# Busboard_v10.net
KiCad netlist of a schematic drawn in EAGLE
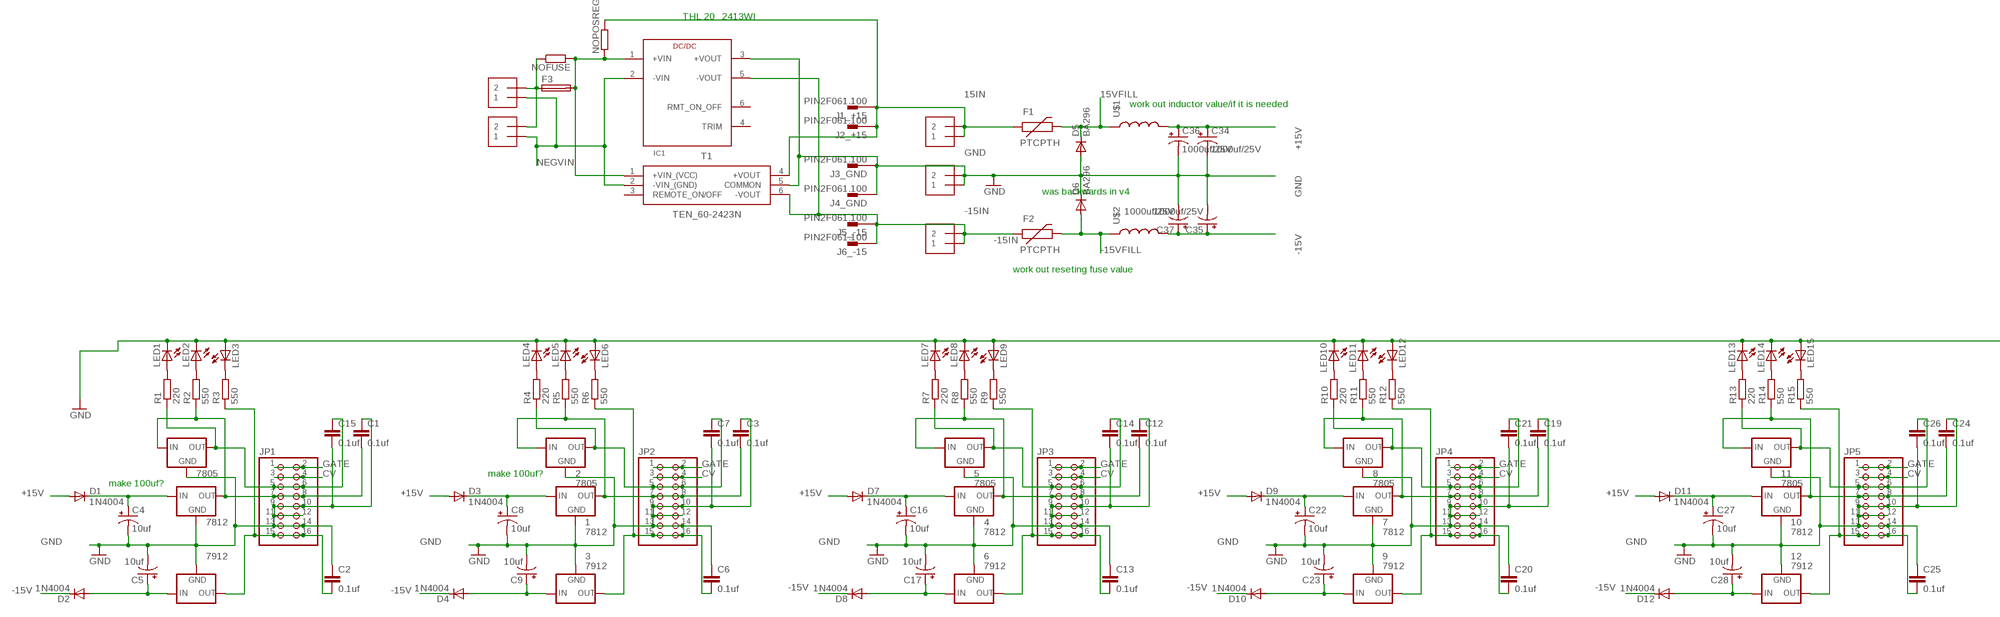
[diagram p0: schematic, sheet 1, part 1 of 2]
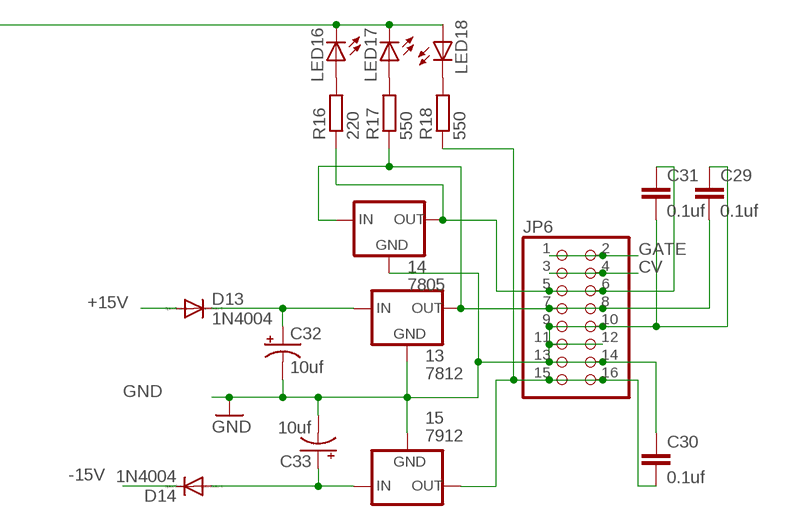
[diagram p1: schematic, sheet 1, part 2 of 2]

(export (version "E")
  (design (tool "Eeschema 10.0.6"))
  (components
    (comp (ref "+15V_DC_IN")
      (value "1X2-3.5MM")
      (footprint "eagle-import:1X2-3.5MM")
      (libsource (lib "eagle-import") (part "1X2-3.5MM"))
    )
    (comp (ref "-15V_DC_IN")
      (value "1X2-3.5MM")
      (footprint "eagle-import:1X2-3.5MM")
      (libsource (lib "eagle-import") (part "1X2-3.5MM"))
    )
    (comp (ref "1")
      (value "7812")
      (footprint "eagle-import:78MXXS")
      (libsource (lib "eagle-import") (part "78MXXS"))
    )
    (comp (ref "2")
      (value "7805")
      (footprint "eagle-import:78MXXS")
      (libsource (lib "eagle-import") (part "78MXXS"))
    )
    (comp (ref "3")
      (value "7912")
      (footprint "eagle-import:79XXS")
      (libsource (lib "eagle-import") (part "79XXS"))
    )
    (comp (ref "4")
      (value "7812")
      (footprint "eagle-import:78MXXS")
      (libsource (lib "eagle-import") (part "78MXXS"))
    )
    (comp (ref "5")
      (value "7805")
      (footprint "eagle-import:78MXXS")
      (libsource (lib "eagle-import") (part "78MXXS"))
    )
    (comp (ref "6")
      (value "7912")
      (footprint "eagle-import:79XXS")
      (libsource (lib "eagle-import") (part "79XXS"))
    )
    (comp (ref "7")
      (value "7812")
      (footprint "eagle-import:78MXXS")
      (libsource (lib "eagle-import") (part "78MXXS"))
    )
    (comp (ref "8")
      (value "7805")
      (footprint "eagle-import:78MXXS")
      (libsource (lib "eagle-import") (part "78MXXS"))
    )
    (comp (ref "9")
      (value "7912")
      (footprint "eagle-import:79XXS")
      (libsource (lib "eagle-import") (part "79XXS"))
    )
    (comp (ref "10")
      (value "7812")
      (footprint "eagle-import:78MXXS")
      (libsource (lib "eagle-import") (part "78MXXS"))
    )
    (comp (ref "11")
      (value "7805")
      (footprint "eagle-import:78MXXS")
      (libsource (lib "eagle-import") (part "78MXXS"))
    )
    (comp (ref "12")
      (value "7912")
      (footprint "eagle-import:79XXS")
      (libsource (lib "eagle-import") (part "79XXS"))
    )
    (comp (ref "13")
      (value "7812")
      (footprint "eagle-import:78MXXS")
      (libsource (lib "eagle-import") (part "78MXXS"))
    )
    (comp (ref "14")
      (value "7805")
      (footprint "eagle-import:78MXXS")
      (libsource (lib "eagle-import") (part "78MXXS"))
    )
    (comp (ref "15")
      (value "7912")
      (footprint "eagle-import:79XXS")
      (libsource (lib "eagle-import") (part "79XXS"))
    )
    (comp (ref "7805")
      (value "78MXXS")
      (footprint "eagle-import:78MXXS")
      (libsource (lib "eagle-import") (part "78MXXS"))
    )
    (comp (ref "7812")
      (value "78MXXS")
      (footprint "eagle-import:78MXXS")
      (libsource (lib "eagle-import") (part "78MXXS"))
    )
    (comp (ref "7912")
      (value "79XXS")
      (footprint "eagle-import:79XXS")
      (libsource (lib "eagle-import") (part "79XXS"))
    )
    (comp (ref "C1")
      (value "0.1uf")
      (footprint "eagle-import:CAP-PTH-SMALL-KIT")
      (libsource (lib "eagle-import") (part "0.1UF-50V-20%(PTH)KIT-EZ"))
    )
    (comp (ref "C2")
      (value "0.1uf")
      (footprint "eagle-import:CAP-PTH-SMALL-KIT")
      (libsource (lib "eagle-import") (part "0.1UF-50V-20%(PTH)KIT-EZ"))
    )
    (comp (ref "C3")
      (value "0.1uf")
      (footprint "eagle-import:CAP-PTH-SMALL-KIT")
      (libsource (lib "eagle-import") (part "0.1UF-50V-20%(PTH)KIT-EZ"))
    )
    (comp (ref "C4")
      (value "10uf")
      (footprint "eagle-import:CPOL-RADIAL-10UF-25V")
      (libsource (lib "eagle-import") (part "10UF-25V-20%(PTH)"))
    )
    (comp (ref "C5")
      (value "10uf")
      (footprint "eagle-import:CPOL-RADIAL-10UF-25V")
      (libsource (lib "eagle-import") (part "10UF-25V-20%(PTH)"))
    )
    (comp (ref "C6")
      (value "0.1uf")
      (footprint "eagle-import:CAP-PTH-SMALL-KIT")
      (libsource (lib "eagle-import") (part "0.1UF-50V-20%(PTH)KIT-EZ"))
    )
    (comp (ref "C7")
      (value "0.1uf")
      (footprint "eagle-import:CAP-PTH-SMALL-KIT")
      (libsource (lib "eagle-import") (part "0.1UF-50V-20%(PTH)KIT-EZ"))
    )
    (comp (ref "C8")
      (value "10uf")
      (footprint "eagle-import:CPOL-RADIAL-10UF-25V")
      (libsource (lib "eagle-import") (part "10UF-25V-20%(PTH)"))
    )
    (comp (ref "C9")
      (value "10uf")
      (footprint "eagle-import:CPOL-RADIAL-10UF-25V")
      (libsource (lib "eagle-import") (part "10UF-25V-20%(PTH)"))
    )
    (comp (ref "C12")
      (value "0.1uf")
      (footprint "eagle-import:CAP-PTH-SMALL-KIT")
      (libsource (lib "eagle-import") (part "0.1UF-50V-20%(PTH)KIT-EZ"))
    )
    (comp (ref "C13")
      (value "0.1uf")
      (footprint "eagle-import:CAP-PTH-SMALL-KIT")
      (libsource (lib "eagle-import") (part "0.1UF-50V-20%(PTH)KIT-EZ"))
    )
    (comp (ref "C14")
      (value "0.1uf")
      (footprint "eagle-import:CAP-PTH-SMALL-KIT")
      (libsource (lib "eagle-import") (part "0.1UF-50V-20%(PTH)KIT-EZ"))
    )
    (comp (ref "C15")
      (value "0.1uf")
      (footprint "eagle-import:CAP-PTH-SMALL-KIT")
      (libsource (lib "eagle-import") (part "0.1UF-50V-20%(PTH)KIT-EZ"))
    )
    (comp (ref "C16")
      (value "10uf")
      (footprint "eagle-import:CPOL-RADIAL-10UF-25V")
      (libsource (lib "eagle-import") (part "10UF-25V-20%(PTH)"))
    )
    (comp (ref "C17")
      (value "10uf")
      (footprint "eagle-import:CPOL-RADIAL-10UF-25V")
      (libsource (lib "eagle-import") (part "10UF-25V-20%(PTH)"))
    )
    (comp (ref "C19")
      (value "0.1uf")
      (footprint "eagle-import:CAP-PTH-SMALL-KIT")
      (libsource (lib "eagle-import") (part "0.1UF-50V-20%(PTH)KIT-EZ"))
    )
    (comp (ref "C20")
      (value "0.1uf")
      (footprint "eagle-import:CAP-PTH-SMALL-KIT")
      (libsource (lib "eagle-import") (part "0.1UF-50V-20%(PTH)KIT-EZ"))
    )
    (comp (ref "C21")
      (value "0.1uf")
      (footprint "eagle-import:CAP-PTH-SMALL-KIT")
      (libsource (lib "eagle-import") (part "0.1UF-50V-20%(PTH)KIT-EZ"))
    )
    (comp (ref "C22")
      (value "10uf")
      (footprint "eagle-import:CPOL-RADIAL-10UF-25V")
      (libsource (lib "eagle-import") (part "10UF-25V-20%(PTH)"))
    )
    (comp (ref "C23")
      (value "10uf")
      (footprint "eagle-import:CPOL-RADIAL-10UF-25V")
      (libsource (lib "eagle-import") (part "10UF-25V-20%(PTH)"))
    )
    (comp (ref "C24")
      (value "0.1uf")
      (footprint "eagle-import:CAP-PTH-SMALL-KIT")
      (libsource (lib "eagle-import") (part "0.1UF-50V-20%(PTH)KIT-EZ"))
    )
    (comp (ref "C25")
      (value "0.1uf")
      (footprint "eagle-import:CAP-PTH-SMALL-KIT")
      (libsource (lib "eagle-import") (part "0.1UF-50V-20%(PTH)KIT-EZ"))
    )
    (comp (ref "C26")
      (value "0.1uf")
      (footprint "eagle-import:CAP-PTH-SMALL-KIT")
      (libsource (lib "eagle-import") (part "0.1UF-50V-20%(PTH)KIT-EZ"))
    )
    (comp (ref "C27")
      (value "10uf")
      (footprint "eagle-import:CPOL-RADIAL-10UF-25V")
      (libsource (lib "eagle-import") (part "10UF-25V-20%(PTH)"))
    )
    (comp (ref "C28")
      (value "10uf")
      (footprint "eagle-import:CPOL-RADIAL-10UF-25V")
      (libsource (lib "eagle-import") (part "10UF-25V-20%(PTH)"))
    )
    (comp (ref "C29")
      (value "0.1uf")
      (footprint "eagle-import:CAP-PTH-SMALL-KIT")
      (libsource (lib "eagle-import") (part "0.1UF-50V-20%(PTH)KIT-EZ"))
    )
    (comp (ref "C30")
      (value "0.1uf")
      (footprint "eagle-import:CAP-PTH-SMALL-KIT")
      (libsource (lib "eagle-import") (part "0.1UF-50V-20%(PTH)KIT-EZ"))
    )
    (comp (ref "C31")
      (value "0.1uf")
      (footprint "eagle-import:CAP-PTH-SMALL-KIT")
      (libsource (lib "eagle-import") (part "0.1UF-50V-20%(PTH)KIT-EZ"))
    )
    (comp (ref "C32")
      (value "10uf")
      (footprint "eagle-import:CPOL-RADIAL-10UF-25V")
      (libsource (lib "eagle-import") (part "10UF-25V-20%(PTH)"))
    )
    (comp (ref "C33")
      (value "10uf")
      (footprint "eagle-import:CPOL-RADIAL-10UF-25V")
      (libsource (lib "eagle-import") (part "10UF-25V-20%(PTH)"))
    )
    (comp (ref "C34")
      (value "1000uf/25V")
      (footprint "eagle-import:CPOL-RADIAL-1000UF-25V-KIT")
      (libsource (lib "eagle-import") (part "1000UF-25V(PTH)KIT"))
    )
    (comp (ref "C35")
      (value "1000uf/25V")
      (footprint "eagle-import:CPOL-RADIAL-1000UF-25V-KIT")
      (libsource (lib "eagle-import") (part "1000UF-25V(PTH)KIT"))
    )
    (comp (ref "C36")
      (value "1000uf/25V")
      (footprint "eagle-import:CPOL-RADIAL-1000UF-25V-KIT")
      (libsource (lib "eagle-import") (part "1000UF-25V(PTH)KIT"))
    )
    (comp (ref "C37")
      (value "1000uf/25V")
      (footprint "eagle-import:CPOL-RADIAL-1000UF-25V-KIT")
      (libsource (lib "eagle-import") (part "1000UF-25V(PTH)KIT"))
    )
    (comp (ref "D1")
      (value "1N4004")
      (footprint "eagle-import:DO41-10")
      (libsource (lib "eagle-import") (part "1N4004"))
    )
    (comp (ref "D2")
      (value "1N4004")
      (footprint "eagle-import:DO41-10")
      (libsource (lib "eagle-import") (part "1N4004"))
    )
    (comp (ref "D3")
      (value "1N4004")
      (footprint "eagle-import:DO41-10")
      (libsource (lib "eagle-import") (part "1N4004"))
    )
    (comp (ref "D4")
      (value "1N4004")
      (footprint "eagle-import:DO41-10")
      (libsource (lib "eagle-import") (part "1N4004"))
    )
    (comp (ref "D5")
      (value "BA296")
      (footprint "eagle-import:P2-15")
      (libsource (lib "eagle-import") (part "BA296"))
    )
    (comp (ref "D6")
      (value "BA296")
      (footprint "eagle-import:P2-15")
      (libsource (lib "eagle-import") (part "BA296"))
    )
    (comp (ref "D7")
      (value "1N4004")
      (footprint "eagle-import:DO41-10")
      (libsource (lib "eagle-import") (part "1N4004"))
    )
    (comp (ref "D8")
      (value "1N4004")
      (footprint "eagle-import:DO41-10")
      (libsource (lib "eagle-import") (part "1N4004"))
    )
    (comp (ref "D9")
      (value "1N4004")
      (footprint "eagle-import:DO41-10")
      (libsource (lib "eagle-import") (part "1N4004"))
    )
    (comp (ref "D10")
      (value "1N4004")
      (footprint "eagle-import:DO41-10")
      (libsource (lib "eagle-import") (part "1N4004"))
    )
    (comp (ref "D11")
      (value "1N4004")
      (footprint "eagle-import:DO41-10")
      (libsource (lib "eagle-import") (part "1N4004"))
    )
    (comp (ref "D12")
      (value "1N4004")
      (footprint "eagle-import:DO41-10")
      (libsource (lib "eagle-import") (part "1N4004"))
    )
    (comp (ref "D13")
      (value "1N4004")
      (footprint "eagle-import:DO41-10")
      (libsource (lib "eagle-import") (part "1N4004"))
    )
    (comp (ref "D14")
      (value "1N4004")
      (footprint "eagle-import:DO41-10")
      (libsource (lib "eagle-import") (part "1N4004"))
    )
    (comp (ref "DC_IN")
      (value "1X2-3.5MM")
      (footprint "eagle-import:1X2-3.5MM")
      (libsource (lib "eagle-import") (part "1X2-3.5MM"))
    )
    (comp (ref "DC_IO")
      (value "1X2-3.5MM")
      (footprint "eagle-import:1X2-3.5MM")
      (libsource (lib "eagle-import") (part "1X2-3.5MM"))
    )
    (comp (ref "F1")
      (value "PTCPTH")
      (footprint "eagle-import:PTC")
      (libsource (lib "eagle-import") (part "PTCPTH"))
    )
    (comp (ref "F2")
      (value "PTCPTH")
      (footprint "eagle-import:PTC")
      (libsource (lib "eagle-import") (part "PTCPTH"))
    )
    (comp (ref "F3")
      (value "GSH15")
      (footprint "eagle-import:GSH15")
      (fields (field (name "MPN") "64900001039"))
      (libsource (lib "eagle-import") (part "GSH15"))
    )
    (comp (ref "GND_IN")
      (value "1X2-3.5MM")
      (footprint "eagle-import:1X2-3.5MM")
      (libsource (lib "eagle-import") (part "1X2-3.5MM"))
    )
    (comp (ref "IC1")
      (value "THL_20WI_SERIES")
      (footprint "eagle-import:THL_20WI_SERIES")
      (libsource (lib "eagle-import") (part "THL_20WI_SERIES"))
    )
    (comp (ref "J1_+15")
      (value "PIN2F061.100")
      (footprint "eagle-import:F061.100")
      (libsource (lib "eagle-import") (part "PIN2F061.100"))
    )
    (comp (ref "J2_+15")
      (value "PIN2F061.100")
      (footprint "eagle-import:F061.100")
      (libsource (lib "eagle-import") (part "PIN2F061.100"))
    )
    (comp (ref "J3_GND")
      (value "PIN2F061.100")
      (footprint "eagle-import:F061.100")
      (libsource (lib "eagle-import") (part "PIN2F061.100"))
    )
    (comp (ref "J4_GND")
      (value "PIN2F061.100")
      (footprint "eagle-import:F061.100")
      (libsource (lib "eagle-import") (part "PIN2F061.100"))
    )
    (comp (ref "J5_-15")
      (value "PIN2F061.100")
      (footprint "eagle-import:F061.100")
      (libsource (lib "eagle-import") (part "PIN2F061.100"))
    )
    (comp (ref "J6_-15")
      (value "PIN2F061.100")
      (footprint "eagle-import:F061.100")
      (libsource (lib "eagle-import") (part "PIN2F061.100"))
    )
    (comp (ref "JP1")
      (value "PINHD-2X8")
      (footprint "eagle-import:2X08")
      (libsource (lib "eagle-import") (part "PINHD-2X8"))
    )
    (comp (ref "JP2")
      (value "PINHD-2X8")
      (footprint "eagle-import:2X08")
      (libsource (lib "eagle-import") (part "PINHD-2X8"))
    )
    (comp (ref "JP3")
      (value "PINHD-2X8")
      (footprint "eagle-import:2X08")
      (libsource (lib "eagle-import") (part "PINHD-2X8"))
    )
    (comp (ref "JP4")
      (value "PINHD-2X8")
      (footprint "eagle-import:2X08")
      (libsource (lib "eagle-import") (part "PINHD-2X8"))
    )
    (comp (ref "JP5")
      (value "PINHD-2X8")
      (footprint "eagle-import:2X08")
      (libsource (lib "eagle-import") (part "PINHD-2X8"))
    )
    (comp (ref "JP6")
      (value "PINHD-2X8")
      (footprint "eagle-import:2X08")
      (libsource (lib "eagle-import") (part "PINHD-2X8"))
    )
    (comp (ref "LED1")
      (value "LED3MM")
      (footprint "eagle-import:LED3MM")
      (libsource (lib "eagle-import") (part "LED3MM"))
    )
    (comp (ref "LED2")
      (value "LED3MM")
      (footprint "eagle-import:LED3MM")
      (libsource (lib "eagle-import") (part "LED3MM"))
    )
    (comp (ref "LED3")
      (value "LED3MM")
      (footprint "eagle-import:LED3MM")
      (libsource (lib "eagle-import") (part "LED3MM"))
    )
    (comp (ref "LED4")
      (value "LED3MM")
      (footprint "eagle-import:LED3MM")
      (libsource (lib "eagle-import") (part "LED3MM"))
    )
    (comp (ref "LED5")
      (value "LED3MM")
      (footprint "eagle-import:LED3MM")
      (libsource (lib "eagle-import") (part "LED3MM"))
    )
    (comp (ref "LED6")
      (value "LED3MM")
      (footprint "eagle-import:LED3MM")
      (libsource (lib "eagle-import") (part "LED3MM"))
    )
    (comp (ref "LED7")
      (value "LED3MM")
      (footprint "eagle-import:LED3MM")
      (libsource (lib "eagle-import") (part "LED3MM"))
    )
    (comp (ref "LED8")
      (value "LED3MM")
      (footprint "eagle-import:LED3MM")
      (libsource (lib "eagle-import") (part "LED3MM"))
    )
    (comp (ref "LED9")
      (value "LED3MM")
      (footprint "eagle-import:LED3MM")
      (libsource (lib "eagle-import") (part "LED3MM"))
    )
    (comp (ref "LED10")
      (value "LED3MM")
      (footprint "eagle-import:LED3MM")
      (libsource (lib "eagle-import") (part "LED3MM"))
    )
    (comp (ref "LED11")
      (value "LED3MM")
      (footprint "eagle-import:LED3MM")
      (libsource (lib "eagle-import") (part "LED3MM"))
    )
    (comp (ref "LED12")
      (value "LED3MM")
      (footprint "eagle-import:LED3MM")
      (libsource (lib "eagle-import") (part "LED3MM"))
    )
    (comp (ref "LED13")
      (value "LED3MM")
      (footprint "eagle-import:LED3MM")
      (libsource (lib "eagle-import") (part "LED3MM"))
    )
    (comp (ref "LED14")
      (value "LED3MM")
      (footprint "eagle-import:LED3MM")
      (libsource (lib "eagle-import") (part "LED3MM"))
    )
    (comp (ref "LED15")
      (value "LED3MM")
      (footprint "eagle-import:LED3MM")
      (libsource (lib "eagle-import") (part "LED3MM"))
    )
    (comp (ref "LED16")
      (value "LED3MM")
      (footprint "eagle-import:LED3MM")
      (libsource (lib "eagle-import") (part "LED3MM"))
    )
    (comp (ref "LED17")
      (value "LED3MM")
      (footprint "eagle-import:LED3MM")
      (libsource (lib "eagle-import") (part "LED3MM"))
    )
    (comp (ref "LED18")
      (value "LED3MM")
      (footprint "eagle-import:LED3MM")
      (libsource (lib "eagle-import") (part "LED3MM"))
    )
    (comp (ref "NOFUSE")
      (value "SMT-REF")
      (footprint "eagle-import:SMT-REF")
      (libsource (lib "eagle-import") (part "SMT-REF"))
    )
    (comp (ref "NOPOSREG")
      (value "SMT-REF")
      (footprint "eagle-import:SMT-REF")
      (libsource (lib "eagle-import") (part "SMT-REF"))
    )
    (comp (ref "R1")
      (value "220")
      (footprint "eagle-import:0207_5V")
      (libsource (lib "eagle-import") (part "R-EU_0207/5V"))
    )
    (comp (ref "R2")
      (value "550")
      (footprint "eagle-import:0207_5V")
      (libsource (lib "eagle-import") (part "R-EU_0207/5V"))
    )
    (comp (ref "R3")
      (value "550")
      (footprint "eagle-import:0207_5V")
      (libsource (lib "eagle-import") (part "R-EU_0207/5V"))
    )
    (comp (ref "R4")
      (value "220")
      (footprint "eagle-import:0207_5V")
      (libsource (lib "eagle-import") (part "R-EU_0207/5V"))
    )
    (comp (ref "R5")
      (value "550")
      (footprint "eagle-import:0207_5V")
      (libsource (lib "eagle-import") (part "R-EU_0207/5V"))
    )
    (comp (ref "R6")
      (value "550")
      (footprint "eagle-import:0207_5V")
      (libsource (lib "eagle-import") (part "R-EU_0207/5V"))
    )
    (comp (ref "R7")
      (value "220")
      (footprint "eagle-import:0207_5V")
      (libsource (lib "eagle-import") (part "R-EU_0207/5V"))
    )
    (comp (ref "R8")
      (value "550")
      (footprint "eagle-import:0207_5V")
      (libsource (lib "eagle-import") (part "R-EU_0207/5V"))
    )
    (comp (ref "R9")
      (value "550")
      (footprint "eagle-import:0207_5V")
      (libsource (lib "eagle-import") (part "R-EU_0207/5V"))
    )
    (comp (ref "R10")
      (value "220")
      (footprint "eagle-import:0207_5V")
      (libsource (lib "eagle-import") (part "R-EU_0207/5V"))
    )
    (comp (ref "R11")
      (value "550")
      (footprint "eagle-import:0207_5V")
      (libsource (lib "eagle-import") (part "R-EU_0207/5V"))
    )
    (comp (ref "R12")
      (value "550")
      (footprint "eagle-import:0207_5V")
      (libsource (lib "eagle-import") (part "R-EU_0207/5V"))
    )
    (comp (ref "R13")
      (value "220")
      (footprint "eagle-import:0207_5V")
      (libsource (lib "eagle-import") (part "R-EU_0207/5V"))
    )
    (comp (ref "R14")
      (value "550")
      (footprint "eagle-import:0207_5V")
      (libsource (lib "eagle-import") (part "R-EU_0207/5V"))
    )
    (comp (ref "R15")
      (value "550")
      (footprint "eagle-import:0207_5V")
      (libsource (lib "eagle-import") (part "R-EU_0207/5V"))
    )
    (comp (ref "R16")
      (value "220")
      (footprint "eagle-import:0207_5V")
      (libsource (lib "eagle-import") (part "R-EU_0207/5V"))
    )
    (comp (ref "R17")
      (value "550")
      (footprint "eagle-import:0207_5V")
      (libsource (lib "eagle-import") (part "R-EU_0207/5V"))
    )
    (comp (ref "R18")
      (value "550")
      (footprint "eagle-import:0207_5V")
      (libsource (lib "eagle-import") (part "R-EU_0207/5V"))
    )
    (comp (ref "T1")
      (value "TEN_60-2423N")
      (footprint "eagle-import:TEN60-2423N")
      (fields
        (field (name "MANUFACTURER_PART_NUMBER") "TEN 60-2423N")
        (field (name "RS_PART_NUMBER") "7882705")
      )
      (libsource (lib "eagle-import") (part "TEN_60-2423N"))
    )
    (comp (ref "U$1")
      (value "INDUCTORRLB0912")
      (footprint "eagle-import:RLB0912")
      (libsource (lib "eagle-import") (part "INDUCTORRLB0912"))
    )
    (comp (ref "U$2")
      (value "INDUCTORRLB0912")
      (footprint "eagle-import:RLB0912")
      (libsource (lib "eagle-import") (part "INDUCTORRLB0912"))
    )
  )
  (nets
    (net (code "1") (name "/+15V") (class "Default")
      (node (ref "C34") (pin "+") (pinfunction "+_+") (pintype "passive"))
      (node (ref "C36") (pin "+") (pinfunction "+_+") (pintype "passive"))
      (node (ref "D1") (pin "A") (pinfunction "A_A") (pintype "passive"))
      (node (ref "D11") (pin "A") (pinfunction "A_A") (pintype "passive"))
      (node (ref "D13") (pin "A") (pinfunction "A_A") (pintype "passive"))
      (node (ref "D3") (pin "A") (pinfunction "A_A") (pintype "passive"))
      (node (ref "D7") (pin "A") (pinfunction "A_A") (pintype "passive"))
      (node (ref "D9") (pin "A") (pinfunction "A_A") (pintype "passive"))
      (node (ref "U$1") (pin "2") (pinfunction "2_2") (pintype "passive"))
    )
    (net (code "2") (name "/-15IN") (class "Default")
      (node (ref "-15V_DC_IN") (pin "1") (pinfunction "1_1") (pintype "passive"))
      (node (ref "-15V_DC_IN") (pin "2") (pinfunction "2_2") (pintype "passive"))
      (node (ref "F2") (pin "P$1") (pinfunction "1_P$1") (pintype "bidirectional"))
      (node (ref "IC1") (pin "5") (pinfunction "-VOUT_5") (pintype "passive"))
      (node (ref "J5_-15") (pin "A1") (pinfunction "1_A1") (pintype "passive"))
      (node (ref "J5_-15") (pin "A2") (pinfunction "1_A2") (pintype "passive"))
      (node (ref "J6_-15") (pin "A1") (pinfunction "1_A1") (pintype "passive"))
      (node (ref "J6_-15") (pin "A2") (pinfunction "1_A2") (pintype "passive"))
      (node (ref "T1") (pin "6") (pinfunction "-VOUT_6") (pintype "passive"))
    )
    (net (code "3") (name "/-15V") (class "Default")
      (node (ref "C35") (pin "+") (pinfunction "+_+") (pintype "passive"))
      (node (ref "C37") (pin "+") (pinfunction "+_+") (pintype "passive"))
      (node (ref "D10") (pin "C") (pinfunction "C_C") (pintype "passive"))
      (node (ref "D12") (pin "C") (pinfunction "C_C") (pintype "passive"))
      (node (ref "D14") (pin "C") (pinfunction "C_C") (pintype "passive"))
      (node (ref "D2") (pin "C") (pinfunction "C_C") (pintype "passive"))
      (node (ref "D4") (pin "C") (pinfunction "C_C") (pintype "passive"))
      (node (ref "D8") (pin "C") (pinfunction "C_C") (pintype "passive"))
      (node (ref "U$2") (pin "2") (pinfunction "2_2") (pintype "passive"))
    )
    (net (code "4") (name "/-15VFILL") (class "Default")
      (node (ref "D6") (pin "A") (pinfunction "A_A") (pintype "passive"))
      (node (ref "F2") (pin "P$2") (pinfunction "2_P$2") (pintype "bidirectional"))
      (node (ref "U$2") (pin "1") (pinfunction "1_1") (pintype "passive"))
    )
    (net (code "5") (name "/15IN") (class "Default")
      (node (ref "+15V_DC_IN") (pin "1") (pinfunction "1_1") (pintype "passive"))
      (node (ref "+15V_DC_IN") (pin "2") (pinfunction "2_2") (pintype "passive"))
      (node (ref "F1") (pin "P$1") (pinfunction "1_P$1") (pintype "bidirectional"))
      (node (ref "J1_+15") (pin "A1") (pinfunction "1_A1") (pintype "passive"))
      (node (ref "J1_+15") (pin "A2") (pinfunction "1_A2") (pintype "passive"))
      (node (ref "J2_+15") (pin "A1") (pinfunction "1_A1") (pintype "passive"))
      (node (ref "J2_+15") (pin "A2") (pinfunction "1_A2") (pintype "passive"))
      (node (ref "NOPOSREG") (pin "1") (pinfunction "1_1") (pintype "passive"))
      (node (ref "T1") (pin "4") (pinfunction "+VOUT_4") (pintype "passive"))
    )
    (net (code "6") (name "/15VFILL") (class "Default")
      (node (ref "D5") (pin "C") (pinfunction "C_C") (pintype "passive"))
      (node (ref "F1") (pin "P$2") (pinfunction "2_P$2") (pintype "bidirectional"))
      (node (ref "U$1") (pin "1") (pinfunction "1_1") (pintype "passive"))
    )
    (net (code "7") (name "/CV") (class "Default")
      (node (ref "JP1") (pin "3") (pinfunction "3_3") (pintype "passive"))
      (node (ref "JP1") (pin "4") (pinfunction "4_4") (pintype "passive"))
      (node (ref "JP2") (pin "3") (pinfunction "3_3") (pintype "passive"))
      (node (ref "JP2") (pin "4") (pinfunction "4_4") (pintype "passive"))
      (node (ref "JP3") (pin "3") (pinfunction "3_3") (pintype "passive"))
      (node (ref "JP3") (pin "4") (pinfunction "4_4") (pintype "passive"))
      (node (ref "JP4") (pin "3") (pinfunction "3_3") (pintype "passive"))
      (node (ref "JP4") (pin "4") (pinfunction "4_4") (pintype "passive"))
      (node (ref "JP5") (pin "3") (pinfunction "3_3") (pintype "passive"))
      (node (ref "JP5") (pin "4") (pinfunction "4_4") (pintype "passive"))
      (node (ref "JP6") (pin "3") (pinfunction "3_3") (pintype "passive"))
      (node (ref "JP6") (pin "4") (pinfunction "4_4") (pintype "passive"))
    )
    (net (code "8") (name "/GATE") (class "Default")
      (node (ref "JP1") (pin "1") (pinfunction "1_1") (pintype "passive"))
      (node (ref "JP1") (pin "2") (pinfunction "2_2") (pintype "passive"))
      (node (ref "JP2") (pin "1") (pinfunction "1_1") (pintype "passive"))
      (node (ref "JP2") (pin "2") (pinfunction "2_2") (pintype "passive"))
      (node (ref "JP3") (pin "1") (pinfunction "1_1") (pintype "passive"))
      (node (ref "JP3") (pin "2") (pinfunction "2_2") (pintype "passive"))
      (node (ref "JP4") (pin "1") (pinfunction "1_1") (pintype "passive"))
      (node (ref "JP4") (pin "2") (pinfunction "2_2") (pintype "passive"))
      (node (ref "JP5") (pin "1") (pinfunction "1_1") (pintype "passive"))
      (node (ref "JP5") (pin "2") (pinfunction "2_2") (pintype "passive"))
      (node (ref "JP6") (pin "1") (pinfunction "1_1") (pintype "passive"))
      (node (ref "JP6") (pin "2") (pinfunction "2_2") (pintype "passive"))
    )
    (net (code "9") (name "/NEGVIN") (class "Default")
      (node (ref "DC_IN") (pin "1") (pinfunction "1_1") (pintype "passive"))
      (node (ref "DC_IO") (pin "1") (pinfunction "1_1") (pintype "passive"))
      (node (ref "IC1") (pin "2") (pinfunction "-VIN_2") (pintype "input"))
      (node (ref "T1") (pin "2") (pinfunction "-VIN_(GND)_2") (pintype "passive"))
    )
    (net (code "10") (name "GND") (class "Default")
      (node (ref "1") (pin "GND") (pinfunction "GND_GND") (pintype "input"))
      (node (ref "10") (pin "GND") (pinfunction "GND_GND") (pintype "input"))
      (node (ref "11") (pin "GND") (pinfunction "GND_GND") (pintype "input"))
      (node (ref "12") (pin "GND") (pinfunction "GND_GND") (pintype "input"))
      (node (ref "13") (pin "GND") (pinfunction "GND_GND") (pintype "input"))
      (node (ref "14") (pin "GND") (pinfunction "GND_GND") (pintype "input"))
      (node (ref "15") (pin "GND") (pinfunction "GND_GND") (pintype "input"))
      (node (ref "2") (pin "GND") (pinfunction "GND_GND") (pintype "input"))
      (node (ref "3") (pin "GND") (pinfunction "GND_GND") (pintype "input"))
      (node (ref "4") (pin "GND") (pinfunction "GND_GND") (pintype "input"))
      (node (ref "5") (pin "GND") (pinfunction "GND_GND") (pintype "input"))
      (node (ref "6") (pin "GND") (pinfunction "GND_GND") (pintype "input"))
      (node (ref "7") (pin "GND") (pinfunction "GND_GND") (pintype "input"))
      (node (ref "7805") (pin "GND") (pinfunction "GND_GND") (pintype "input"))
      (node (ref "7812") (pin "GND") (pinfunction "GND_GND") (pintype "input"))
      (node (ref "7912") (pin "GND") (pinfunction "GND_GND") (pintype "input"))
      (node (ref "8") (pin "GND") (pinfunction "GND_GND") (pintype "input"))
      (node (ref "9") (pin "GND") (pinfunction "GND_GND") (pintype "input"))
      (node (ref "C1") (pin "1") (pinfunction "1_1") (pintype "passive"))
      (node (ref "C12") (pin "1") (pinfunction "1_1") (pintype "passive"))
      (node (ref "C13") (pin "1") (pinfunction "1_1") (pintype "passive"))
      (node (ref "C14") (pin "2") (pinfunction "2_2") (pintype "passive"))
      (node (ref "C15") (pin "2") (pinfunction "2_2") (pintype "passive"))
      (node (ref "C16") (pin "2") (pinfunction "-_2") (pintype "passive"))
      (node (ref "C17") (pin "2") (pinfunction "-_2") (pintype "passive"))
      (node (ref "C19") (pin "1") (pinfunction "1_1") (pintype "passive"))
      (node (ref "C2") (pin "1") (pinfunction "1_1") (pintype "passive"))
      (node (ref "C20") (pin "1") (pinfunction "1_1") (pintype "passive"))
      (node (ref "C21") (pin "2") (pinfunction "2_2") (pintype "passive"))
      (node (ref "C22") (pin "2") (pinfunction "-_2") (pintype "passive"))
      (node (ref "C23") (pin "2") (pinfunction "-_2") (pintype "passive"))
      (node (ref "C24") (pin "1") (pinfunction "1_1") (pintype "passive"))
      (node (ref "C25") (pin "1") (pinfunction "1_1") (pintype "passive"))
      (node (ref "C26") (pin "2") (pinfunction "2_2") (pintype "passive"))
      (node (ref "C27") (pin "2") (pinfunction "-_2") (pintype "passive"))
      (node (ref "C28") (pin "2") (pinfunction "-_2") (pintype "passive"))
      (node (ref "C29") (pin "1") (pinfunction "1_1") (pintype "passive"))
      (node (ref "C3") (pin "1") (pinfunction "1_1") (pintype "passive"))
      (node (ref "C30") (pin "1") (pinfunction "1_1") (pintype "passive"))
      (node (ref "C31") (pin "2") (pinfunction "2_2") (pintype "passive"))
      (node (ref "C32") (pin "2") (pinfunction "-_2") (pintype "passive"))
      (node (ref "C33") (pin "2") (pinfunction "-_2") (pintype "passive"))
      (node (ref "C34") (pin "-") (pinfunction "-_-") (pintype "passive"))
      (node (ref "C35") (pin "-") (pinfunction "-_-") (pintype "passive"))
      (node (ref "C36") (pin "-") (pinfunction "-_-") (pintype "passive"))
      (node (ref "C37") (pin "-") (pinfunction "-_-") (pintype "passive"))
      (node (ref "C4") (pin "2") (pinfunction "-_2") (pintype "passive"))
      (node (ref "C5") (pin "2") (pinfunction "-_2") (pintype "passive"))
      (node (ref "C6") (pin "1") (pinfunction "1_1") (pintype "passive"))
      (node (ref "C7") (pin "2") (pinfunction "2_2") (pintype "passive"))
      (node (ref "C8") (pin "2") (pinfunction "-_2") (pintype "passive"))
      (node (ref "C9") (pin "2") (pinfunction "-_2") (pintype "passive"))
      (node (ref "D5") (pin "A") (pinfunction "A_A") (pintype "passive"))
      (node (ref "D6") (pin "C") (pinfunction "C_C") (pintype "passive"))
      (node (ref "GND_IN") (pin "1") (pinfunction "1_1") (pintype "passive"))
      (node (ref "GND_IN") (pin "2") (pinfunction "2_2") (pintype "passive"))
      (node (ref "IC1") (pin "3") (pinfunction "+VOUT_3") (pintype "passive"))
      (node (ref "J3_GND") (pin "A1") (pinfunction "1_A1") (pintype "passive"))
      (node (ref "J3_GND") (pin "A2") (pinfunction "1_A2") (pintype "passive"))
      (node (ref "J4_GND") (pin "A1") (pinfunction "1_A1") (pintype "passive"))
      (node (ref "J4_GND") (pin "A2") (pinfunction "1_A2") (pintype "passive"))
      (node (ref "JP1") (pin "10") (pinfunction "10_10") (pintype "passive"))
      (node (ref "JP1") (pin "11") (pinfunction "11_11") (pintype "passive"))
      (node (ref "JP1") (pin "12") (pinfunction "12_12") (pintype "passive"))
      (node (ref "JP1") (pin "13") (pinfunction "13_13") (pintype "passive"))
      (node (ref "JP1") (pin "14") (pinfunction "14_14") (pintype "passive"))
      (node (ref "JP1") (pin "9") (pinfunction "9_9") (pintype "passive"))
      (node (ref "JP2") (pin "10") (pinfunction "10_10") (pintype "passive"))
      (node (ref "JP2") (pin "11") (pinfunction "11_11") (pintype "passive"))
      (node (ref "JP2") (pin "12") (pinfunction "12_12") (pintype "passive"))
      (node (ref "JP2") (pin "13") (pinfunction "13_13") (pintype "passive"))
      (node (ref "JP2") (pin "14") (pinfunction "14_14") (pintype "passive"))
      (node (ref "JP2") (pin "9") (pinfunction "9_9") (pintype "passive"))
      (node (ref "JP3") (pin "10") (pinfunction "10_10") (pintype "passive"))
      (node (ref "JP3") (pin "11") (pinfunction "11_11") (pintype "passive"))
      (node (ref "JP3") (pin "12") (pinfunction "12_12") (pintype "passive"))
      (node (ref "JP3") (pin "13") (pinfunction "13_13") (pintype "passive"))
      (node (ref "JP3") (pin "14") (pinfunction "14_14") (pintype "passive"))
      (node (ref "JP3") (pin "9") (pinfunction "9_9") (pintype "passive"))
      (node (ref "JP4") (pin "10") (pinfunction "10_10") (pintype "passive"))
      (node (ref "JP4") (pin "11") (pinfunction "11_11") (pintype "passive"))
      (node (ref "JP4") (pin "12") (pinfunction "12_12") (pintype "passive"))
      (node (ref "JP4") (pin "13") (pinfunction "13_13") (pintype "passive"))
      (node (ref "JP4") (pin "14") (pinfunction "14_14") (pintype "passive"))
      (node (ref "JP4") (pin "9") (pinfunction "9_9") (pintype "passive"))
      (node (ref "JP5") (pin "10") (pinfunction "10_10") (pintype "passive"))
      (node (ref "JP5") (pin "11") (pinfunction "11_11") (pintype "passive"))
      (node (ref "JP5") (pin "12") (pinfunction "12_12") (pintype "passive"))
      (node (ref "JP5") (pin "13") (pinfunction "13_13") (pintype "passive"))
      (node (ref "JP5") (pin "14") (pinfunction "14_14") (pintype "passive"))
      (node (ref "JP5") (pin "9") (pinfunction "9_9") (pintype "passive"))
      (node (ref "JP6") (pin "10") (pinfunction "10_10") (pintype "passive"))
      (node (ref "JP6") (pin "11") (pinfunction "11_11") (pintype "passive"))
      (node (ref "JP6") (pin "12") (pinfunction "12_12") (pintype "passive"))
      (node (ref "JP6") (pin "13") (pinfunction "13_13") (pintype "passive"))
      (node (ref "JP6") (pin "14") (pinfunction "14_14") (pintype "passive"))
      (node (ref "JP6") (pin "9") (pinfunction "9_9") (pintype "passive"))
      (node (ref "LED1") (pin "K") (pinfunction "C_K") (pintype "passive"))
      (node (ref "LED10") (pin "K") (pinfunction "C_K") (pintype "passive"))
      (node (ref "LED11") (pin "K") (pinfunction "C_K") (pintype "passive"))
      (node (ref "LED12") (pin "A") (pinfunction "A_A") (pintype "passive"))
      (node (ref "LED13") (pin "K") (pinfunction "C_K") (pintype "passive"))
      (node (ref "LED14") (pin "K") (pinfunction "C_K") (pintype "passive"))
      (node (ref "LED15") (pin "A") (pinfunction "A_A") (pintype "passive"))
      (node (ref "LED16") (pin "K") (pinfunction "C_K") (pintype "passive"))
      (node (ref "LED17") (pin "K") (pinfunction "C_K") (pintype "passive"))
      (node (ref "LED18") (pin "A") (pinfunction "A_A") (pintype "passive"))
      (node (ref "LED2") (pin "K") (pinfunction "C_K") (pintype "passive"))
      (node (ref "LED3") (pin "A") (pinfunction "A_A") (pintype "passive"))
      (node (ref "LED4") (pin "K") (pinfunction "C_K") (pintype "passive"))
      (node (ref "LED5") (pin "K") (pinfunction "C_K") (pintype "passive"))
      (node (ref "LED6") (pin "A") (pinfunction "A_A") (pintype "passive"))
      (node (ref "LED7") (pin "K") (pinfunction "C_K") (pintype "passive"))
      (node (ref "LED8") (pin "K") (pinfunction "C_K") (pintype "passive"))
      (node (ref "LED9") (pin "A") (pinfunction "A_A") (pintype "passive"))
      (node (ref "T1") (pin "5") (pinfunction "COMMON_5") (pintype "passive"))
    )
    (net (code "11") (name "Net-(1-PadOUT)") (class "Default")
      (node (ref "1") (pin "OUT") (pinfunction "OUT_OUT") (pintype "passive"))
      (node (ref "2") (pin "IN") (pinfunction "IN_IN") (pintype "input"))
      (node (ref "C3") (pin "2") (pinfunction "2_2") (pintype "passive"))
      (node (ref "JP2") (pin "7") (pinfunction "7_7") (pintype "passive"))
      (node (ref "JP2") (pin "8") (pinfunction "8_8") (pintype "passive"))
      (node (ref "R5") (pin "1") (pinfunction "1_1") (pintype "passive"))
    )
    (net (code "12") (name "Net-(2-PadOUT)") (class "Default")
      (node (ref "2") (pin "OUT") (pinfunction "OUT_OUT") (pintype "passive"))
      (node (ref "C7") (pin "1") (pinfunction "1_1") (pintype "passive"))
      (node (ref "JP2") (pin "5") (pinfunction "5_5") (pintype "passive"))
      (node (ref "JP2") (pin "6") (pinfunction "6_6") (pintype "passive"))
      (node (ref "R4") (pin "1") (pinfunction "1_1") (pintype "passive"))
    )
    (net (code "13") (name "Net-(3-PadOUT)") (class "Default")
      (node (ref "3") (pin "OUT") (pinfunction "OUT_OUT") (pintype "passive"))
      (node (ref "C6") (pin "2") (pinfunction "2_2") (pintype "passive"))
      (node (ref "JP2") (pin "15") (pinfunction "15_15") (pintype "passive"))
      (node (ref "JP2") (pin "16") (pinfunction "16_16") (pintype "passive"))
      (node (ref "R6") (pin "1") (pinfunction "1_1") (pintype "passive"))
    )
    (net (code "14") (name "Net-(4-PadOUT)") (class "Default")
      (node (ref "4") (pin "OUT") (pinfunction "OUT_OUT") (pintype "passive"))
      (node (ref "5") (pin "IN") (pinfunction "IN_IN") (pintype "input"))
      (node (ref "C12") (pin "2") (pinfunction "2_2") (pintype "passive"))
      (node (ref "JP3") (pin "7") (pinfunction "7_7") (pintype "passive"))
      (node (ref "JP3") (pin "8") (pinfunction "8_8") (pintype "passive"))
      (node (ref "R8") (pin "1") (pinfunction "1_1") (pintype "passive"))
    )
    (net (code "15") (name "Net-(5-PadOUT)") (class "Default")
      (node (ref "5") (pin "OUT") (pinfunction "OUT_OUT") (pintype "passive"))
      (node (ref "C14") (pin "1") (pinfunction "1_1") (pintype "passive"))
      (node (ref "JP3") (pin "5") (pinfunction "5_5") (pintype "passive"))
      (node (ref "JP3") (pin "6") (pinfunction "6_6") (pintype "passive"))
      (node (ref "R7") (pin "1") (pinfunction "1_1") (pintype "passive"))
    )
    (net (code "16") (name "Net-(6-PadOUT)") (class "Default")
      (node (ref "6") (pin "OUT") (pinfunction "OUT_OUT") (pintype "passive"))
      (node (ref "C13") (pin "2") (pinfunction "2_2") (pintype "passive"))
      (node (ref "JP3") (pin "15") (pinfunction "15_15") (pintype "passive"))
      (node (ref "JP3") (pin "16") (pinfunction "16_16") (pintype "passive"))
      (node (ref "R9") (pin "1") (pinfunction "1_1") (pintype "passive"))
    )
    (net (code "17") (name "Net-(7-PadOUT)") (class "Default")
      (node (ref "7") (pin "OUT") (pinfunction "OUT_OUT") (pintype "passive"))
      (node (ref "8") (pin "IN") (pinfunction "IN_IN") (pintype "input"))
      (node (ref "C19") (pin "2") (pinfunction "2_2") (pintype "passive"))
      (node (ref "JP4") (pin "7") (pinfunction "7_7") (pintype "passive"))
      (node (ref "JP4") (pin "8") (pinfunction "8_8") (pintype "passive"))
      (node (ref "R11") (pin "1") (pinfunction "1_1") (pintype "passive"))
    )
    (net (code "18") (name "Net-(8-PadOUT)") (class "Default")
      (node (ref "8") (pin "OUT") (pinfunction "OUT_OUT") (pintype "passive"))
      (node (ref "C21") (pin "1") (pinfunction "1_1") (pintype "passive"))
      (node (ref "JP4") (pin "5") (pinfunction "5_5") (pintype "passive"))
      (node (ref "JP4") (pin "6") (pinfunction "6_6") (pintype "passive"))
      (node (ref "R10") (pin "1") (pinfunction "1_1") (pintype "passive"))
    )
    (net (code "19") (name "Net-(9-PadOUT)") (class "Default")
      (node (ref "9") (pin "OUT") (pinfunction "OUT_OUT") (pintype "passive"))
      (node (ref "C20") (pin "2") (pinfunction "2_2") (pintype "passive"))
      (node (ref "JP4") (pin "15") (pinfunction "15_15") (pintype "passive"))
      (node (ref "JP4") (pin "16") (pinfunction "16_16") (pintype "passive"))
      (node (ref "R12") (pin "1") (pinfunction "1_1") (pintype "passive"))
    )
    (net (code "20") (name "Net-(10-PadOUT)") (class "Default")
      (node (ref "10") (pin "OUT") (pinfunction "OUT_OUT") (pintype "passive"))
      (node (ref "11") (pin "IN") (pinfunction "IN_IN") (pintype "input"))
      (node (ref "C24") (pin "2") (pinfunction "2_2") (pintype "passive"))
      (node (ref "JP5") (pin "7") (pinfunction "7_7") (pintype "passive"))
      (node (ref "JP5") (pin "8") (pinfunction "8_8") (pintype "passive"))
      (node (ref "R14") (pin "1") (pinfunction "1_1") (pintype "passive"))
    )
    (net (code "21") (name "Net-(11-PadOUT)") (class "Default")
      (node (ref "11") (pin "OUT") (pinfunction "OUT_OUT") (pintype "passive"))
      (node (ref "C26") (pin "1") (pinfunction "1_1") (pintype "passive"))
      (node (ref "JP5") (pin "5") (pinfunction "5_5") (pintype "passive"))
      (node (ref "JP5") (pin "6") (pinfunction "6_6") (pintype "passive"))
      (node (ref "R13") (pin "1") (pinfunction "1_1") (pintype "passive"))
    )
    (net (code "22") (name "Net-(12-PadOUT)") (class "Default")
      (node (ref "12") (pin "OUT") (pinfunction "OUT_OUT") (pintype "passive"))
      (node (ref "C25") (pin "2") (pinfunction "2_2") (pintype "passive"))
      (node (ref "JP5") (pin "15") (pinfunction "15_15") (pintype "passive"))
      (node (ref "JP5") (pin "16") (pinfunction "16_16") (pintype "passive"))
      (node (ref "R15") (pin "1") (pinfunction "1_1") (pintype "passive"))
    )
    (net (code "23") (name "Net-(13-PadOUT)") (class "Default")
      (node (ref "13") (pin "OUT") (pinfunction "OUT_OUT") (pintype "passive"))
      (node (ref "14") (pin "IN") (pinfunction "IN_IN") (pintype "input"))
      (node (ref "C29") (pin "2") (pinfunction "2_2") (pintype "passive"))
      (node (ref "JP6") (pin "7") (pinfunction "7_7") (pintype "passive"))
      (node (ref "JP6") (pin "8") (pinfunction "8_8") (pintype "passive"))
      (node (ref "R17") (pin "1") (pinfunction "1_1") (pintype "passive"))
    )
    (net (code "24") (name "Net-(14-PadOUT)") (class "Default")
      (node (ref "14") (pin "OUT") (pinfunction "OUT_OUT") (pintype "passive"))
      (node (ref "C31") (pin "1") (pinfunction "1_1") (pintype "passive"))
      (node (ref "JP6") (pin "5") (pinfunction "5_5") (pintype "passive"))
      (node (ref "JP6") (pin "6") (pinfunction "6_6") (pintype "passive"))
      (node (ref "R16") (pin "1") (pinfunction "1_1") (pintype "passive"))
    )
    (net (code "25") (name "Net-(15-PadOUT)") (class "Default")
      (node (ref "15") (pin "OUT") (pinfunction "OUT_OUT") (pintype "passive"))
      (node (ref "C30") (pin "2") (pinfunction "2_2") (pintype "passive"))
      (node (ref "JP6") (pin "15") (pinfunction "15_15") (pintype "passive"))
      (node (ref "JP6") (pin "16") (pinfunction "16_16") (pintype "passive"))
      (node (ref "R18") (pin "1") (pinfunction "1_1") (pintype "passive"))
    )
    (net (code "26") (name "Net-(7805-PadIN)") (class "Default")
      (node (ref "7805") (pin "IN") (pinfunction "IN_IN") (pintype "input"))
      (node (ref "7812") (pin "OUT") (pinfunction "OUT_OUT") (pintype "passive"))
      (node (ref "C1") (pin "2") (pinfunction "2_2") (pintype "passive"))
      (node (ref "JP1") (pin "7") (pinfunction "7_7") (pintype "passive"))
      (node (ref "JP1") (pin "8") (pinfunction "8_8") (pintype "passive"))
      (node (ref "R2") (pin "1") (pinfunction "1_1") (pintype "passive"))
    )
    (net (code "27") (name "Net-(7805-PadOUT)") (class "Default")
      (node (ref "7805") (pin "OUT") (pinfunction "OUT_OUT") (pintype "passive"))
      (node (ref "C15") (pin "1") (pinfunction "1_1") (pintype "passive"))
      (node (ref "JP1") (pin "5") (pinfunction "5_5") (pintype "passive"))
      (node (ref "JP1") (pin "6") (pinfunction "6_6") (pintype "passive"))
      (node (ref "R1") (pin "1") (pinfunction "1_1") (pintype "passive"))
    )
    (net (code "28") (name "Net-(7912-PadOUT)") (class "Default")
      (node (ref "7912") (pin "OUT") (pinfunction "OUT_OUT") (pintype "passive"))
      (node (ref "C2") (pin "2") (pinfunction "2_2") (pintype "passive"))
      (node (ref "JP1") (pin "15") (pinfunction "15_15") (pintype "passive"))
      (node (ref "JP1") (pin "16") (pinfunction "16_16") (pintype "passive"))
      (node (ref "R3") (pin "1") (pinfunction "1_1") (pintype "passive"))
    )
    (net (code "29") (name "Net-(C4-+)") (class "Default")
      (node (ref "7812") (pin "IN") (pinfunction "IN_IN") (pintype "input"))
      (node (ref "C4") (pin "1") (pinfunction "+_1") (pintype "passive"))
      (node (ref "D1") (pin "C") (pinfunction "C_C") (pintype "passive"))
    )
    (net (code "30") (name "Net-(C5-+)") (class "Default")
      (node (ref "7912") (pin "IN") (pinfunction "IN_IN") (pintype "input"))
      (node (ref "C5") (pin "1") (pinfunction "+_1") (pintype "passive"))
      (node (ref "D2") (pin "A") (pinfunction "A_A") (pintype "passive"))
    )
    (net (code "31") (name "Net-(C8-+)") (class "Default")
      (node (ref "1") (pin "IN") (pinfunction "IN_IN") (pintype "input"))
      (node (ref "C8") (pin "1") (pinfunction "+_1") (pintype "passive"))
      (node (ref "D3") (pin "C") (pinfunction "C_C") (pintype "passive"))
    )
    (net (code "32") (name "Net-(C9-+)") (class "Default")
      (node (ref "3") (pin "IN") (pinfunction "IN_IN") (pintype "input"))
      (node (ref "C9") (pin "1") (pinfunction "+_1") (pintype "passive"))
      (node (ref "D4") (pin "A") (pinfunction "A_A") (pintype "passive"))
    )
    (net (code "33") (name "Net-(C16-+)") (class "Default")
      (node (ref "4") (pin "IN") (pinfunction "IN_IN") (pintype "input"))
      (node (ref "C16") (pin "1") (pinfunction "+_1") (pintype "passive"))
      (node (ref "D7") (pin "C") (pinfunction "C_C") (pintype "passive"))
    )
    (net (code "34") (name "Net-(C17-+)") (class "Default")
      (node (ref "6") (pin "IN") (pinfunction "IN_IN") (pintype "input"))
      (node (ref "C17") (pin "1") (pinfunction "+_1") (pintype "passive"))
      (node (ref "D8") (pin "A") (pinfunction "A_A") (pintype "passive"))
    )
    (net (code "35") (name "Net-(C22-+)") (class "Default")
      (node (ref "7") (pin "IN") (pinfunction "IN_IN") (pintype "input"))
      (node (ref "C22") (pin "1") (pinfunction "+_1") (pintype "passive"))
      (node (ref "D9") (pin "C") (pinfunction "C_C") (pintype "passive"))
    )
    (net (code "36") (name "Net-(C23-+)") (class "Default")
      (node (ref "9") (pin "IN") (pinfunction "IN_IN") (pintype "input"))
      (node (ref "C23") (pin "1") (pinfunction "+_1") (pintype "passive"))
      (node (ref "D10") (pin "A") (pinfunction "A_A") (pintype "passive"))
    )
    (net (code "37") (name "Net-(C27-+)") (class "Default")
      (node (ref "10") (pin "IN") (pinfunction "IN_IN") (pintype "input"))
      (node (ref "C27") (pin "1") (pinfunction "+_1") (pintype "passive"))
      (node (ref "D11") (pin "C") (pinfunction "C_C") (pintype "passive"))
    )
    (net (code "38") (name "Net-(C28-+)") (class "Default")
      (node (ref "12") (pin "IN") (pinfunction "IN_IN") (pintype "input"))
      (node (ref "C28") (pin "1") (pinfunction "+_1") (pintype "passive"))
      (node (ref "D12") (pin "A") (pinfunction "A_A") (pintype "passive"))
    )
    (net (code "39") (name "Net-(C32-+)") (class "Default")
      (node (ref "13") (pin "IN") (pinfunction "IN_IN") (pintype "input"))
      (node (ref "C32") (pin "1") (pinfunction "+_1") (pintype "passive"))
      (node (ref "D13") (pin "C") (pinfunction "C_C") (pintype "passive"))
    )
    (net (code "40") (name "Net-(C33-+)") (class "Default")
      (node (ref "15") (pin "IN") (pinfunction "IN_IN") (pintype "input"))
      (node (ref "C33") (pin "1") (pinfunction "+_1") (pintype "passive"))
      (node (ref "D14") (pin "A") (pinfunction "A_A") (pintype "passive"))
    )
    (net (code "41") (name "Net-(DC_IN-Pad2)") (class "Default")
      (node (ref "DC_IN") (pin "2") (pinfunction "2_2") (pintype "passive"))
      (node (ref "DC_IO") (pin "2") (pinfunction "2_2") (pintype "passive"))
      (node (ref "F3") (pin "1") (pinfunction "1_1") (pintype "passive"))
      (node (ref "NOFUSE") (pin "1") (pinfunction "1_1") (pintype "passive"))
    )
    (net (code "42") (name "Net-(IC1-+VIN)") (class "Default")
      (node (ref "F3") (pin "2") (pinfunction "2_2") (pintype "passive"))
      (node (ref "IC1") (pin "1") (pinfunction "+VIN_1") (pintype "input"))
      (node (ref "NOFUSE") (pin "2") (pinfunction "2_2") (pintype "passive"))
      (node (ref "NOPOSREG") (pin "2") (pinfunction "2_2") (pintype "passive"))
      (node (ref "T1") (pin "1") (pinfunction "+VIN_(VCC)_1") (pintype "passive"))
    )
    (net (code "43") (name "Net-(LED1-PadA)") (class "Default")
      (node (ref "LED1") (pin "A") (pinfunction "A_A") (pintype "passive"))
      (node (ref "R1") (pin "2") (pinfunction "2_2") (pintype "passive"))
    )
    (net (code "44") (name "Net-(LED2-PadA)") (class "Default")
      (node (ref "LED2") (pin "A") (pinfunction "A_A") (pintype "passive"))
      (node (ref "R2") (pin "2") (pinfunction "2_2") (pintype "passive"))
    )
    (net (code "45") (name "Net-(LED3-C)") (class "Default")
      (node (ref "LED3") (pin "K") (pinfunction "C_K") (pintype "passive"))
      (node (ref "R3") (pin "2") (pinfunction "2_2") (pintype "passive"))
    )
    (net (code "46") (name "Net-(LED4-PadA)") (class "Default")
      (node (ref "LED4") (pin "A") (pinfunction "A_A") (pintype "passive"))
      (node (ref "R4") (pin "2") (pinfunction "2_2") (pintype "passive"))
    )
    (net (code "47") (name "Net-(LED5-PadA)") (class "Default")
      (node (ref "LED5") (pin "A") (pinfunction "A_A") (pintype "passive"))
      (node (ref "R5") (pin "2") (pinfunction "2_2") (pintype "passive"))
    )
    (net (code "48") (name "Net-(LED6-C)") (class "Default")
      (node (ref "LED6") (pin "K") (pinfunction "C_K") (pintype "passive"))
      (node (ref "R6") (pin "2") (pinfunction "2_2") (pintype "passive"))
    )
    (net (code "49") (name "Net-(LED7-PadA)") (class "Default")
      (node (ref "LED7") (pin "A") (pinfunction "A_A") (pintype "passive"))
      (node (ref "R7") (pin "2") (pinfunction "2_2") (pintype "passive"))
    )
    (net (code "50") (name "Net-(LED8-PadA)") (class "Default")
      (node (ref "LED8") (pin "A") (pinfunction "A_A") (pintype "passive"))
      (node (ref "R8") (pin "2") (pinfunction "2_2") (pintype "passive"))
    )
    (net (code "51") (name "Net-(LED9-C)") (class "Default")
      (node (ref "LED9") (pin "K") (pinfunction "C_K") (pintype "passive"))
      (node (ref "R9") (pin "2") (pinfunction "2_2") (pintype "passive"))
    )
    (net (code "52") (name "Net-(LED10-PadA)") (class "Default")
      (node (ref "LED10") (pin "A") (pinfunction "A_A") (pintype "passive"))
      (node (ref "R10") (pin "2") (pinfunction "2_2") (pintype "passive"))
    )
    (net (code "53") (name "Net-(LED11-PadA)") (class "Default")
      (node (ref "LED11") (pin "A") (pinfunction "A_A") (pintype "passive"))
      (node (ref "R11") (pin "2") (pinfunction "2_2") (pintype "passive"))
    )
    (net (code "54") (name "Net-(LED12-C)") (class "Default")
      (node (ref "LED12") (pin "K") (pinfunction "C_K") (pintype "passive"))
      (node (ref "R12") (pin "2") (pinfunction "2_2") (pintype "passive"))
    )
    (net (code "55") (name "Net-(LED13-PadA)") (class "Default")
      (node (ref "LED13") (pin "A") (pinfunction "A_A") (pintype "passive"))
      (node (ref "R13") (pin "2") (pinfunction "2_2") (pintype "passive"))
    )
    (net (code "56") (name "Net-(LED14-PadA)") (class "Default")
      (node (ref "LED14") (pin "A") (pinfunction "A_A") (pintype "passive"))
      (node (ref "R14") (pin "2") (pinfunction "2_2") (pintype "passive"))
    )
    (net (code "57") (name "Net-(LED15-C)") (class "Default")
      (node (ref "LED15") (pin "K") (pinfunction "C_K") (pintype "passive"))
      (node (ref "R15") (pin "2") (pinfunction "2_2") (pintype "passive"))
    )
    (net (code "58") (name "Net-(LED16-PadA)") (class "Default")
      (node (ref "LED16") (pin "A") (pinfunction "A_A") (pintype "passive"))
      (node (ref "R16") (pin "2") (pinfunction "2_2") (pintype "passive"))
    )
    (net (code "59") (name "Net-(LED17-PadA)") (class "Default")
      (node (ref "LED17") (pin "A") (pinfunction "A_A") (pintype "passive"))
      (node (ref "R17") (pin "2") (pinfunction "2_2") (pintype "passive"))
    )
    (net (code "60") (name "Net-(LED18-C)") (class "Default")
      (node (ref "LED18") (pin "K") (pinfunction "C_K") (pintype "passive"))
      (node (ref "R18") (pin "2") (pinfunction "2_2") (pintype "passive"))
    )
    (net (code "61") (name "unconnected-(IC1-RMT_ON_OFF-Pad6)") (class "Default")
      (node (ref "IC1") (pin "6") (pinfunction "RMT_ON_OFF_6") (pintype "input"))
    )
    (net (code "62") (name "unconnected-(IC1-TRIM-Pad4)") (class "Default")
      (node (ref "IC1") (pin "4") (pinfunction "TRIM_4") (pintype "input"))
    )
    (net (code "63") (name "unconnected-(T1-REMOTE_ON{slash}OFF-Pad3)") (class "Default")
      (node (ref "T1") (pin "3") (pinfunction "REMOTE_ON/OFF_3") (pintype "passive"))
    )
  )
)
